# Simple_NPN_Regen_Receiver.net
KiCad netlist of a schematic drawn in EAGLE
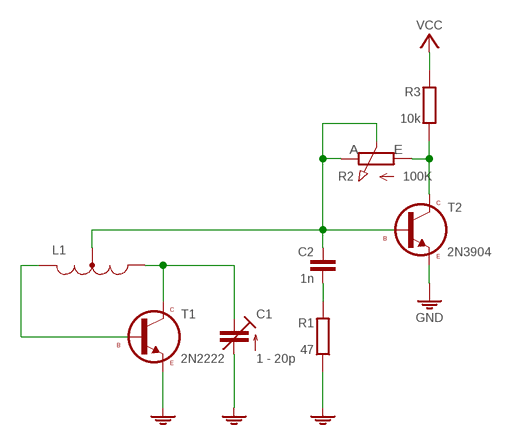
[diagram p0: schematic, sheet 1]

(export (version "E")
  (design (tool "Eeschema 10.0.6"))
  (components
    (comp (ref "C1")
      (value "1 - 20p")
      (footprint "eagle-import:TRIM-2222-808")
      (libsource (lib "eagle-import") (part "C-TR-PH201272222-808-2PINB"))
    )
    (comp (ref "C2")
      (value "1n")
      (footprint "eagle-import:C025-024X044")
      (libsource (lib "eagle-import") (part "C025-024X044"))
    )
    (comp (ref "L1")
      (value "L-H-TAPM-08/20V")
      (footprint "eagle-import:L-08_20V-TAPM")
      (libsource (lib "eagle-import") (part "L-H-TAPM-08/20V"))
    )
    (comp (ref "R1")
      (value "47")
      (footprint "eagle-import:0204_10-V")
      (libsource (lib "eagle-import") (part "R0204/10-V"))
    )
    (comp (ref "R2")
      (value "100K")
      (footprint "eagle-import:POT")
      (libsource (lib "eagle-import") (part "POT-H"))
    )
    (comp (ref "R3")
      (value "10k")
      (footprint "eagle-import:0202_10-V")
      (libsource (lib "eagle-import") (part "R0202/10-V"))
    )
    (comp (ref "S3")
      (value "VCC_GNDR")
      (footprint "eagle-import:SPAD+-")
      (libsource (lib "eagle-import") (part "VCC_GNDR"))
    )
    (comp (ref "T1")
      (value "2N2222")
      (footprint "eagle-import:TO92")
      (libsource (lib "eagle-import") (part "2N2222"))
    )
    (comp (ref "T2")
      (value "2N3904")
      (footprint "eagle-import:TO92-EBC-A")
      (libsource (lib "eagle-import") (part "2N3904-A"))
    )
  )
  (nets
    (net (code "1") (name "GND") (class "Default")
      (node (ref "C1") (pin "3") (pinfunction "A_3") (pintype "passive"))
      (node (ref "R1") (pin "2") (pinfunction "1_2") (pintype "passive"))
      (node (ref "S3") (pin "1") (pinfunction "GND_1") (pintype "power_in"))
      (node (ref "T1") (pin "3") (pinfunction "E_3") (pintype "passive"))
      (node (ref "T2") (pin "E") (pinfunction "E_E") (pintype "passive"))
    )
    (net (code "2") (name "Net-(C1-E)") (class "Default")
      (node (ref "C1") (pin "2") (pinfunction "E_2") (pintype "passive"))
      (node (ref "L1") (pin "2") (pinfunction "2_2") (pintype "passive"))
      (node (ref "T1") (pin "1") (pinfunction "C_1") (pintype "passive"))
    )
    (net (code "3") (name "Net-(C2-Pad1)") (class "Default")
      (node (ref "C2") (pin "1") (pinfunction "1_1") (pintype "passive"))
      (node (ref "L1") (pin "T") (pinfunction "T_T") (pintype "passive"))
      (node (ref "R2") (pin "E") (pinfunction "E_E") (pintype "passive"))
      (node (ref "R2") (pin "S") (pinfunction "S_S") (pintype "passive"))
      (node (ref "T2") (pin "B") (pinfunction "B_B") (pintype "passive"))
    )
    (net (code "4") (name "Net-(L1-3)") (class "Default")
      (node (ref "L1") (pin "1") (pinfunction "3_1") (pintype "passive"))
      (node (ref "T1") (pin "2") (pinfunction "B_2") (pintype "passive"))
    )
    (net (code "5") (name "Net-(R1-2)") (class "Default")
      (node (ref "C2") (pin "2") (pinfunction "2_2") (pintype "passive"))
      (node (ref "R1") (pin "1") (pinfunction "2_1") (pintype "passive"))
    )
    (net (code "6") (name "Net-(R3-1)") (class "Default")
      (node (ref "R2") (pin "A") (pinfunction "A_A") (pintype "passive"))
      (node (ref "R3") (pin "2") (pinfunction "1_2") (pintype "passive"))
      (node (ref "T2") (pin "C") (pinfunction "C_C") (pintype "passive"))
    )
    (net (code "7") (name "Net-(R3-2)") (class "Default")
      (node (ref "R3") (pin "1") (pinfunction "2_1") (pintype "passive"))
      (node (ref "S3") (pin "2") (pinfunction "VCC_2") (pintype "power_in"))
    )
  )
)
